# rapidshark-main-breakout-top-mk-1_0.net
KiCad netlist of a schematic drawn in EAGLE
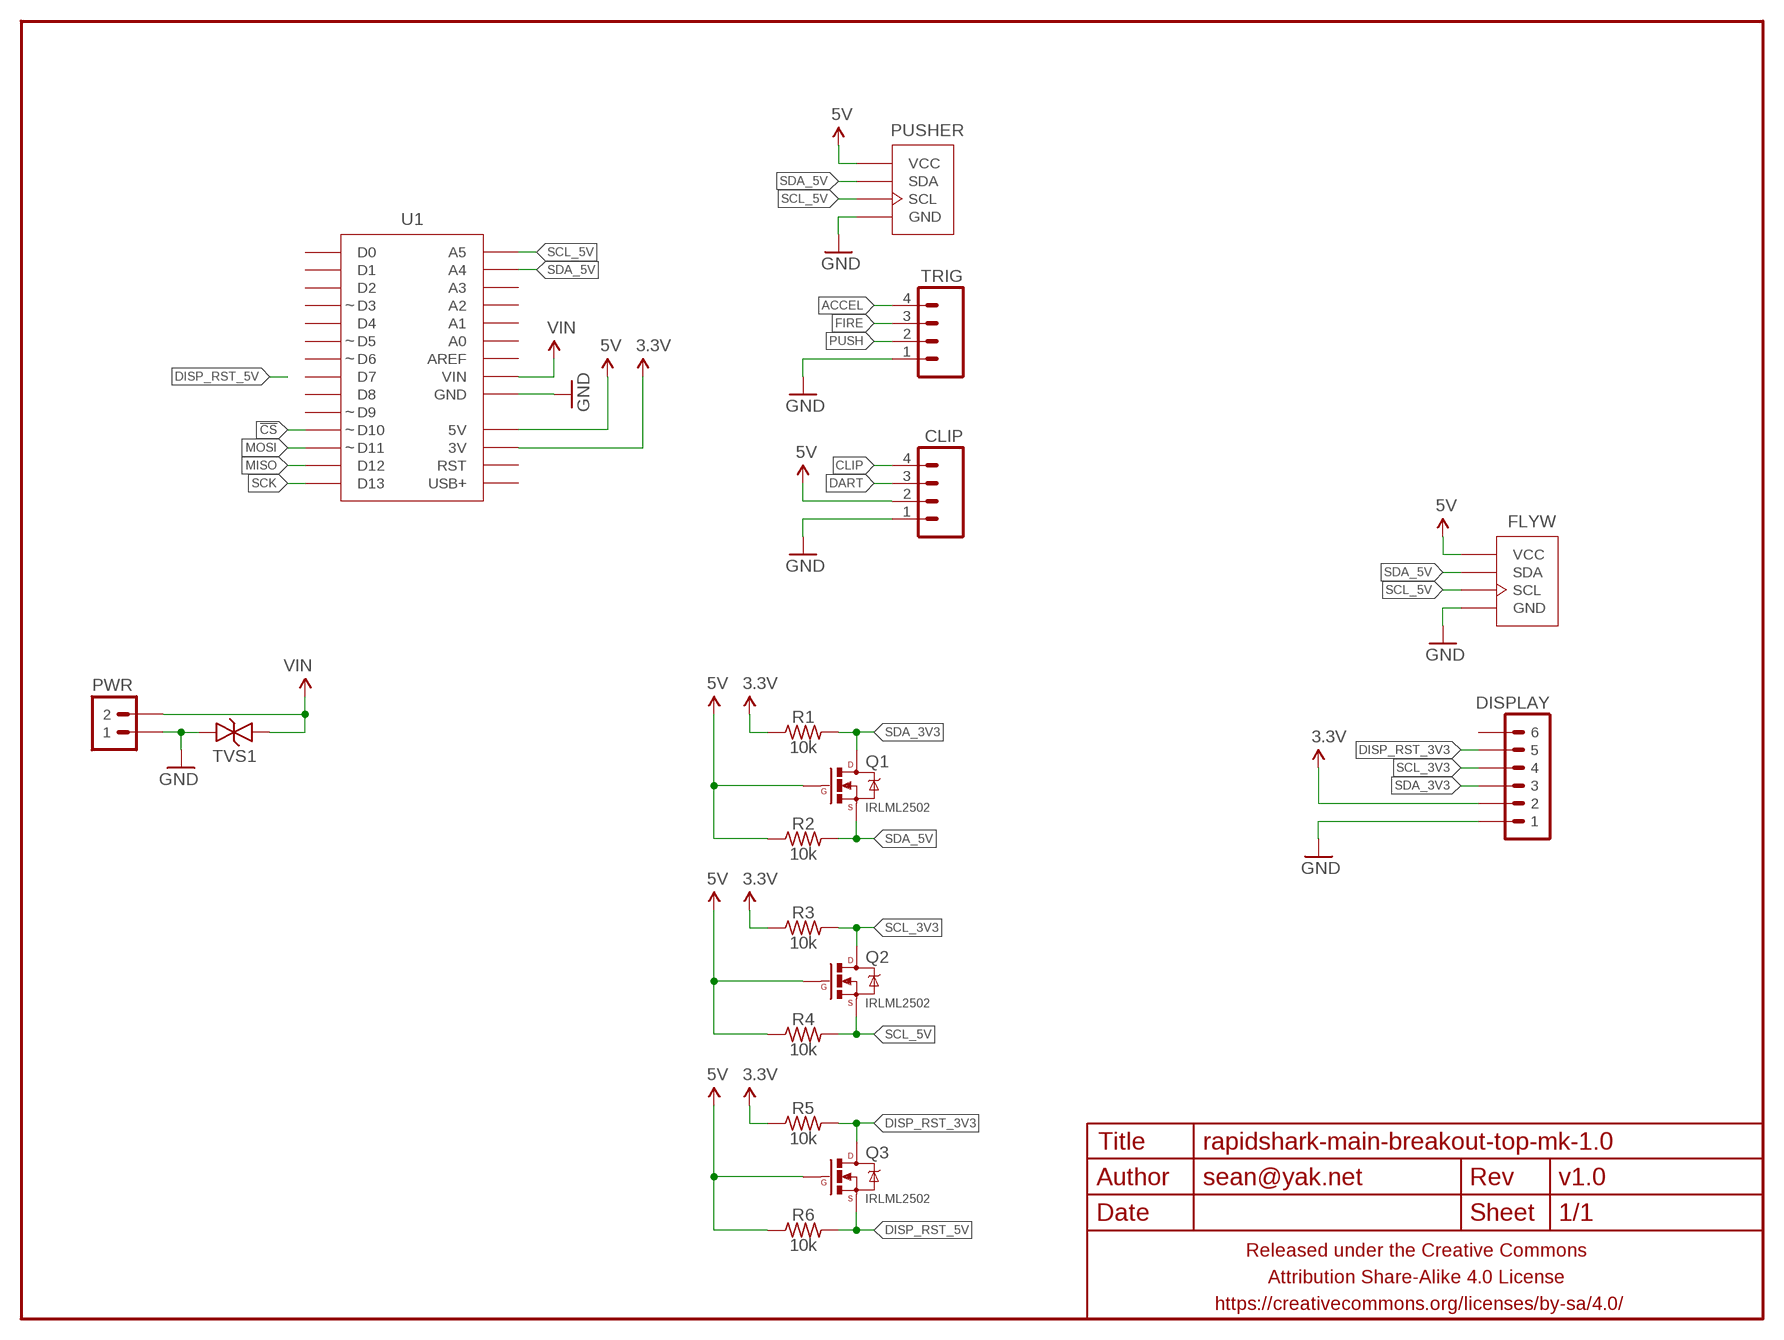
[diagram p0: schematic, sheet 1]

(export (version "E")
  (design (tool "Eeschema 10.0.6"))
  (components
    (comp (ref "CLIP")
      (value "M04JST-PTH-VERT")
      (footprint "eagle-import:JST-4-PH-VERT-PTH")
      (libsource (lib "eagle-import") (part "M04JST-PTH-VERT"))
    )
    (comp (ref "DISPLAY")
      (value "M06JST-PH-PTH-VERT")
      (footprint "eagle-import:JST-6-PH-VERT-PTH")
      (libsource (lib "eagle-import") (part "M06JST-PH-PTH-VERT"))
    )
    (comp (ref "FLYW")
      (value "M04-I2CJST-4-PH-VERT-NS")
      (footprint "eagle-import:JST-4-PH-VERT-PTH")
      (libsource (lib "eagle-import") (part "M04-I2CJST-4-PH-VERT-NS"))
    )
    (comp (ref "FRAME1")
      (value "FRAME-LETTERNO_PACKAGE")
      (footprint "eagle-import:DUMMY")
      (fields (field (name "DESIGNER") "sean@yak.net") (field (name "VERSION") "v1.0"))
      (libsource (lib "eagle-import") (part "FRAME-LETTERNO_PACKAGE"))
    )
    (comp (ref "PUSHER")
      (value "M04-I2CJST-4-PH-VERT-NS")
      (footprint "eagle-import:JST-4-PH-VERT-PTH")
      (libsource (lib "eagle-import") (part "M04-I2CJST-4-PH-VERT-NS"))
    )
    (comp (ref "PWR")
      (value "M02PTH-CENTERED-R+")
      (footprint "eagle-import:1X02-CENTER-R+")
      (libsource (lib "eagle-import") (part "M02PTH-CENTERED-R+"))
    )
    (comp (ref "Q1")
      (value "IRLML2502")
      (footprint "eagle-import:SOT23")
      (libsource (lib "eagle-import") (part "MOSFET-NCHANNELIRLML2502"))
    )
    (comp (ref "Q2")
      (value "IRLML2502")
      (footprint "eagle-import:SOT23")
      (libsource (lib "eagle-import") (part "MOSFET-NCHANNELIRLML2502"))
    )
    (comp (ref "Q3")
      (value "IRLML2502")
      (footprint "eagle-import:SOT23")
      (libsource (lib "eagle-import") (part "MOSFET-NCHANNELIRLML2502"))
    )
    (comp (ref "R1")
      (value "10k")
      (footprint "eagle-import:R0603")
      (libsource (lib "eagle-import") (part "RESISTORR0603"))
    )
    (comp (ref "R2")
      (value "10k")
      (footprint "eagle-import:R0603")
      (libsource (lib "eagle-import") (part "RESISTORR0603"))
    )
    (comp (ref "R3")
      (value "10k")
      (footprint "eagle-import:R0603")
      (libsource (lib "eagle-import") (part "RESISTORR0603"))
    )
    (comp (ref "R4")
      (value "10k")
      (footprint "eagle-import:R0603")
      (libsource (lib "eagle-import") (part "RESISTORR0603"))
    )
    (comp (ref "R5")
      (value "10k")
      (footprint "eagle-import:R0603")
      (libsource (lib "eagle-import") (part "RESISTORR0603"))
    )
    (comp (ref "R6")
      (value "10k")
      (footprint "eagle-import:R0603")
      (libsource (lib "eagle-import") (part "RESISTORR0603"))
    )
    (comp (ref "TRIG")
      (value "M04JST-PTH-VERT")
      (footprint "eagle-import:JST-4-PH-VERT-PTH")
      (libsource (lib "eagle-import") (part "M04JST-PTH-VERT"))
    )
    (comp (ref "TVS1")
      (value "TVSSMA")
      (footprint "eagle-import:SMA-DIODE-TVS-BIDIR")
      (libsource (lib "eagle-import") (part "TVSSMA"))
    )
    (comp (ref "U1")
      (value "ADAFRUIT_METRO_MININOSILK-ABMBI")
      (footprint "eagle-import:ADAFRUIT_METRO_MINI_FLIPPED")
      (libsource (lib "eagle-import") (part "ADAFRUIT_METRO_MININOSILK-ABMBI"))
    )
  )
  (nets
    (net (code "1") (name "/~{CS}") (class "Default")
      (node (ref "U1") (pin "11") (pinfunction "D10_11") (pintype "bidirectional"))
    )
    (net (code "2") (name "3.3V") (class "Default")
      (node (ref "DISPLAY") (pin "2") (pinfunction "2_2") (pintype "passive"))
      (node (ref "R1") (pin "1") (pinfunction "1_1") (pintype "passive"))
      (node (ref "R3") (pin "1") (pinfunction "1_1") (pintype "passive"))
      (node (ref "R5") (pin "1") (pinfunction "1_1") (pintype "passive"))
      (node (ref "U1") (pin "17") (pinfunction "3V_17") (pintype "bidirectional"))
    )
    (net (code "3") (name "5V") (class "Default")
      (node (ref "CLIP") (pin "2") (pinfunction "2_2") (pintype "passive"))
      (node (ref "FLYW") (pin "2") (pinfunction "VCC_2") (pintype "bidirectional"))
      (node (ref "PUSHER") (pin "2") (pinfunction "VCC_2") (pintype "bidirectional"))
      (node (ref "Q1") (pin "1") (pinfunction "G_1") (pintype "passive"))
      (node (ref "Q2") (pin "1") (pinfunction "G_1") (pintype "passive"))
      (node (ref "Q3") (pin "1") (pinfunction "G_1") (pintype "passive"))
      (node (ref "R2") (pin "1") (pinfunction "1_1") (pintype "passive"))
      (node (ref "R4") (pin "1") (pinfunction "1_1") (pintype "passive"))
      (node (ref "R6") (pin "1") (pinfunction "1_1") (pintype "passive"))
      (node (ref "U1") (pin "18") (pinfunction "5V_18") (pintype "bidirectional"))
    )
    (net (code "4") (name "ACCEL") (class "Default")
      (node (ref "TRIG") (pin "4") (pinfunction "4_4") (pintype "passive"))
    )
    (net (code "5") (name "CLIP") (class "Default")
      (node (ref "CLIP") (pin "4") (pinfunction "4_4") (pintype "passive"))
    )
    (net (code "6") (name "DART") (class "Default")
      (node (ref "CLIP") (pin "3") (pinfunction "3_3") (pintype "passive"))
    )
    (net (code "7") (name "DISP_RST_3V3") (class "Default")
      (node (ref "DISPLAY") (pin "5") (pinfunction "5_5") (pintype "passive"))
      (node (ref "Q3") (pin "3") (pinfunction "D_3") (pintype "passive"))
      (node (ref "R5") (pin "2") (pinfunction "2_2") (pintype "passive"))
    )
    (net (code "8") (name "DISP_RST_5V") (class "Default")
      (node (ref "Q3") (pin "2") (pinfunction "S_2") (pintype "passive"))
      (node (ref "R6") (pin "2") (pinfunction "2_2") (pintype "passive"))
    )
    (net (code "9") (name "FIRE") (class "Default")
      (node (ref "TRIG") (pin "3") (pinfunction "3_3") (pintype "passive"))
    )
    (net (code "10") (name "GND") (class "Default")
      (node (ref "CLIP") (pin "1") (pinfunction "1_1") (pintype "passive"))
      (node (ref "DISPLAY") (pin "1") (pinfunction "1_1") (pintype "passive"))
      (node (ref "FLYW") (pin "1") (pinfunction "GND_1") (pintype "bidirectional"))
      (node (ref "PUSHER") (pin "1") (pinfunction "GND_1") (pintype "bidirectional"))
      (node (ref "PWR") (pin "1") (pinfunction "1_1") (pintype "passive"))
      (node (ref "TRIG") (pin "1") (pinfunction "1_1") (pintype "passive"))
      (node (ref "TVS1") (pin "1") (pinfunction "1_1") (pintype "passive"))
      (node (ref "U1") (pin "19") (pinfunction "GND_19") (pintype "bidirectional"))
      (node (ref "U1") (pin "20") (pinfunction "GND_20") (pintype "bidirectional"))
    )
    (net (code "11") (name "MISO") (class "Default")
      (node (ref "U1") (pin "13") (pinfunction "D12_13") (pintype "bidirectional"))
    )
    (net (code "12") (name "MOSI") (class "Default")
      (node (ref "U1") (pin "12") (pinfunction "D11_12") (pintype "bidirectional"))
    )
    (net (code "13") (name "PUSH") (class "Default")
      (node (ref "TRIG") (pin "2") (pinfunction "2_2") (pintype "passive"))
    )
    (net (code "14") (name "SCK") (class "Default")
      (node (ref "U1") (pin "14") (pinfunction "D13_14") (pintype "bidirectional"))
    )
    (net (code "15") (name "SCL_3V3") (class "Default")
      (node (ref "DISPLAY") (pin "4") (pinfunction "4_4") (pintype "passive"))
      (node (ref "Q2") (pin "3") (pinfunction "D_3") (pintype "passive"))
      (node (ref "R3") (pin "2") (pinfunction "2_2") (pintype "passive"))
    )
    (net (code "16") (name "SCL_5V") (class "Default")
      (node (ref "FLYW") (pin "4") (pinfunction "SCL_4") (pintype "bidirectional"))
      (node (ref "PUSHER") (pin "4") (pinfunction "SCL_4") (pintype "bidirectional"))
      (node (ref "Q2") (pin "2") (pinfunction "S_2") (pintype "passive"))
      (node (ref "R4") (pin "2") (pinfunction "2_2") (pintype "passive"))
      (node (ref "U1") (pin "28") (pinfunction "A5_28") (pintype "bidirectional"))
    )
    (net (code "17") (name "SDA_3V3") (class "Default")
      (node (ref "DISPLAY") (pin "3") (pinfunction "3_3") (pintype "passive"))
      (node (ref "Q1") (pin "3") (pinfunction "D_3") (pintype "passive"))
      (node (ref "R1") (pin "2") (pinfunction "2_2") (pintype "passive"))
    )
    (net (code "18") (name "SDA_5V") (class "Default")
      (node (ref "FLYW") (pin "3") (pinfunction "SDA_3") (pintype "bidirectional"))
      (node (ref "PUSHER") (pin "3") (pinfunction "SDA_3") (pintype "bidirectional"))
      (node (ref "Q1") (pin "2") (pinfunction "S_2") (pintype "passive"))
      (node (ref "R2") (pin "2") (pinfunction "2_2") (pintype "passive"))
      (node (ref "U1") (pin "27") (pinfunction "A4_27") (pintype "bidirectional"))
    )
    (net (code "19") (name "VIN") (class "Default")
      (node (ref "PWR") (pin "2") (pinfunction "2_2") (pintype "passive"))
      (node (ref "TVS1") (pin "2") (pinfunction "2_2") (pintype "passive"))
      (node (ref "U1") (pin "21") (pinfunction "VIN_21") (pintype "bidirectional"))
    )
    (net (code "20") (name "unconnected-(DISPLAY-Pad6)") (class "Default")
      (node (ref "DISPLAY") (pin "6") (pinfunction "6_6") (pintype "passive"))
    )
    (net (code "21") (name "unconnected-(U1-A0-Pad23)") (class "Default")
      (node (ref "U1") (pin "23") (pinfunction "A0_23") (pintype "bidirectional"))
    )
    (net (code "22") (name "unconnected-(U1-A1-Pad24)") (class "Default")
      (node (ref "U1") (pin "24") (pinfunction "A1_24") (pintype "bidirectional"))
    )
    (net (code "23") (name "unconnected-(U1-A2-Pad25)") (class "Default")
      (node (ref "U1") (pin "25") (pinfunction "A2_25") (pintype "bidirectional"))
    )
    (net (code "24") (name "unconnected-(U1-A3-Pad26)") (class "Default")
      (node (ref "U1") (pin "26") (pinfunction "A3_26") (pintype "bidirectional"))
    )
    (net (code "25") (name "unconnected-(U1-AREF-Pad22)") (class "Default")
      (node (ref "U1") (pin "22") (pinfunction "AREF_22") (pintype "bidirectional"))
    )
    (net (code "26") (name "unconnected-(U1-D0-Pad1)") (class "Default")
      (node (ref "U1") (pin "1") (pinfunction "D0_1") (pintype "bidirectional"))
    )
    (net (code "27") (name "unconnected-(U1-D1-Pad2)") (class "Default")
      (node (ref "U1") (pin "2") (pinfunction "D1_2") (pintype "bidirectional"))
    )
    (net (code "28") (name "unconnected-(U1-D2-Pad3)") (class "Default")
      (node (ref "U1") (pin "3") (pinfunction "D2_3") (pintype "bidirectional"))
    )
    (net (code "29") (name "unconnected-(U1-D3-Pad4)") (class "Default")
      (node (ref "U1") (pin "4") (pinfunction "D3_4") (pintype "bidirectional"))
    )
    (net (code "30") (name "unconnected-(U1-D4-Pad5)") (class "Default")
      (node (ref "U1") (pin "5") (pinfunction "D4_5") (pintype "bidirectional"))
    )
    (net (code "31") (name "unconnected-(U1-D5-Pad6)") (class "Default")
      (node (ref "U1") (pin "6") (pinfunction "D5_6") (pintype "bidirectional"))
    )
    (net (code "32") (name "unconnected-(U1-D6-Pad7)") (class "Default")
      (node (ref "U1") (pin "7") (pinfunction "D6_7") (pintype "bidirectional"))
    )
    (net (code "33") (name "unconnected-(U1-D7-Pad8)") (class "Default")
      (node (ref "U1") (pin "8") (pinfunction "D7_8") (pintype "bidirectional"))
    )
    (net (code "34") (name "unconnected-(U1-D8-Pad9)") (class "Default")
      (node (ref "U1") (pin "9") (pinfunction "D8_9") (pintype "bidirectional"))
    )
    (net (code "35") (name "unconnected-(U1-D9-Pad10)") (class "Default")
      (node (ref "U1") (pin "10") (pinfunction "D9_10") (pintype "bidirectional"))
    )
    (net (code "36") (name "unconnected-(U1-RST-Pad16)") (class "Default")
      (node (ref "U1") (pin "16") (pinfunction "RST_16") (pintype "bidirectional"))
    )
    (net (code "37") (name "unconnected-(U1-USB+-Pad15)") (class "Default")
      (node (ref "U1") (pin "15") (pinfunction "USB+_15") (pintype "bidirectional"))
    )
  )
)
